# RFID_Brd_02.net
KiCad netlist of a schematic drawn in EAGLE
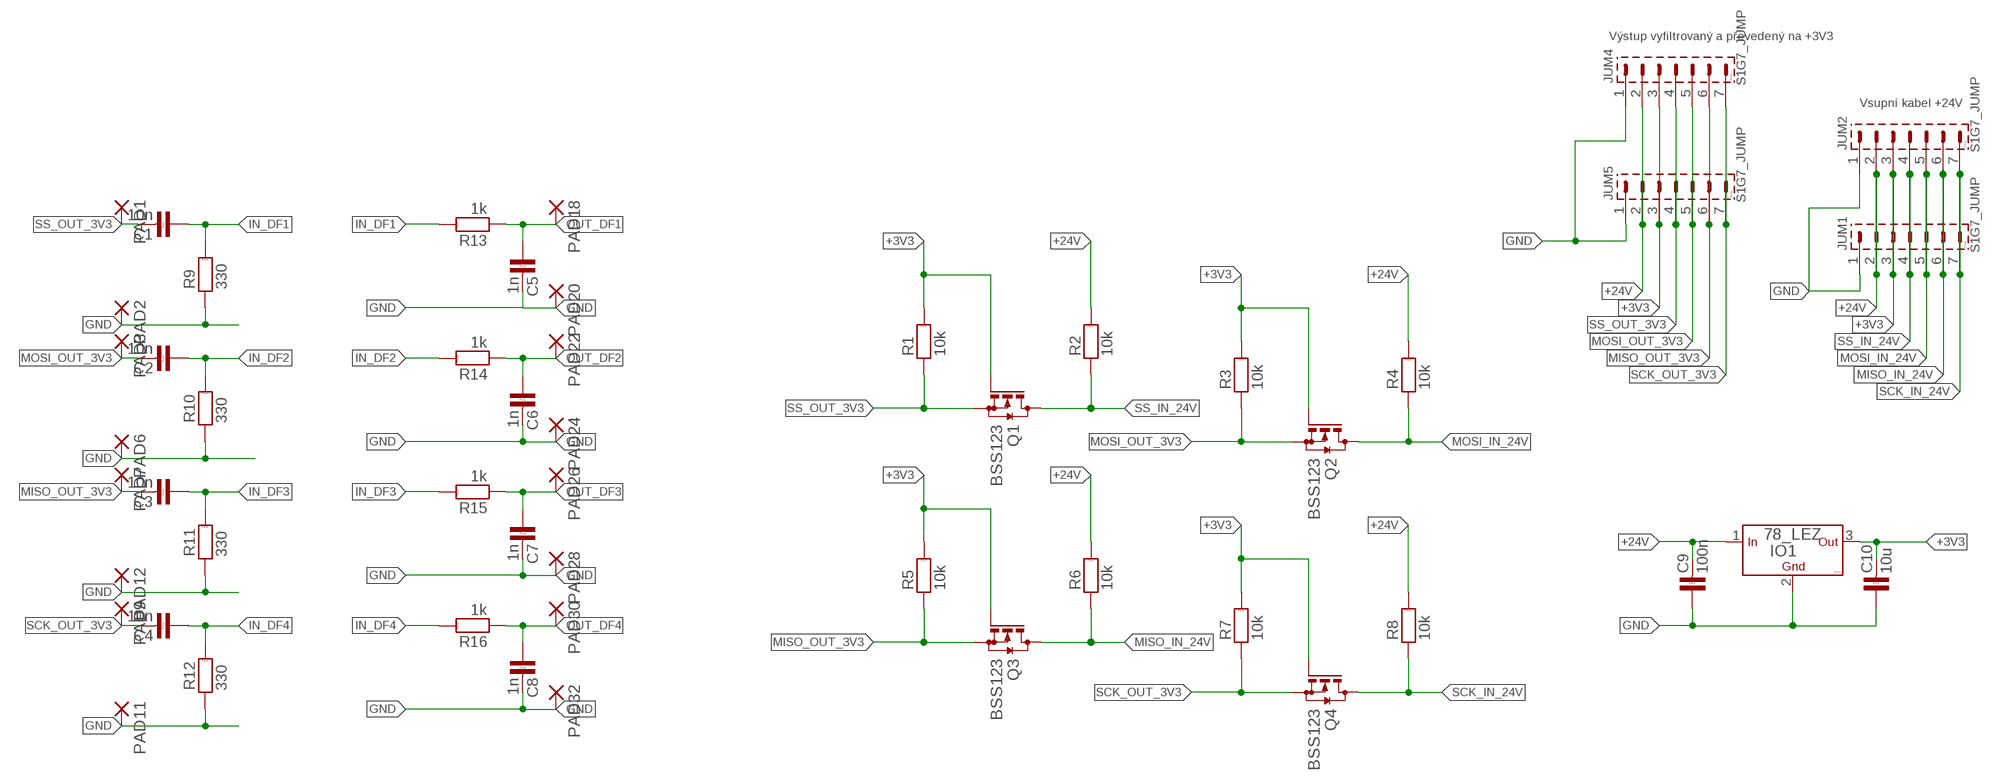
[diagram p0: schematic, sheet 1]

(export (version "E")
  (design (tool "Eeschema 10.0.6"))
  (components
    (comp (ref "C1")
      (value "10n")
      (footprint "eagle-import:1206")
      (libsource (lib "eagle-import") (part "C-KER_1206"))
    )
    (comp (ref "C2")
      (value "10n")
      (footprint "eagle-import:1206")
      (libsource (lib "eagle-import") (part "C-KER_1206"))
    )
    (comp (ref "C3")
      (value "10n")
      (footprint "eagle-import:1206")
      (libsource (lib "eagle-import") (part "C-KER_1206"))
    )
    (comp (ref "C4")
      (value "10n")
      (footprint "eagle-import:1206")
      (libsource (lib "eagle-import") (part "C-KER_1206"))
    )
    (comp (ref "C5")
      (value "1n")
      (footprint "eagle-import:1206")
      (libsource (lib "eagle-import") (part "C-KER_1206"))
    )
    (comp (ref "C6")
      (value "1n")
      (footprint "eagle-import:1206")
      (libsource (lib "eagle-import") (part "C-KER_1206"))
    )
    (comp (ref "C7")
      (value "1n")
      (footprint "eagle-import:1206")
      (libsource (lib "eagle-import") (part "C-KER_1206"))
    )
    (comp (ref "C8")
      (value "1n")
      (footprint "eagle-import:1206")
      (libsource (lib "eagle-import") (part "C-KER_1206"))
    )
    (comp (ref "C9")
      (value "100n")
      (footprint "eagle-import:1206")
      (libsource (lib "eagle-import") (part "C-KER_1206"))
    )
    (comp (ref "C10")
      (value "10u")
      (footprint "eagle-import:1206")
      (libsource (lib "eagle-import") (part "C-KER_1206"))
    )
    (comp (ref "IO1")
      (value "78_LEZ")
      (footprint "eagle-import:TO-220")
      (libsource (lib "eagle-import") (part "78?_LEZ"))
    )
    (comp (ref "JUM1")
      (value "S1G7_JUMP")
      (footprint "eagle-import:S1G7_JUM")
      (libsource (lib "eagle-import") (part "S1G7_JUMP"))
    )
    (comp (ref "JUM2")
      (value "S1G7_JUMP")
      (footprint "eagle-import:S1G7_JUM")
      (libsource (lib "eagle-import") (part "S1G7_JUMP"))
    )
    (comp (ref "JUM4")
      (value "S1G7_JUMP")
      (footprint "eagle-import:S1G7_JUM")
      (libsource (lib "eagle-import") (part "S1G7_JUMP"))
    )
    (comp (ref "JUM5")
      (value "S1G7_JUMP")
      (footprint "eagle-import:S1G7_JUM")
      (libsource (lib "eagle-import") (part "S1G7_JUMP"))
    )
    (comp (ref "PAD1")
      (value "SMD2")
      (footprint "eagle-import:SMD1,27-2,54")
      (libsource (lib "eagle-import") (part "SMD2"))
    )
    (comp (ref "PAD2")
      (value "SMD2")
      (footprint "eagle-import:SMD1,27-2,54")
      (libsource (lib "eagle-import") (part "SMD2"))
    )
    (comp (ref "PAD3")
      (value "SMD2")
      (footprint "eagle-import:SMD1,27-2,54")
      (libsource (lib "eagle-import") (part "SMD2"))
    )
    (comp (ref "PAD6")
      (value "SMD2")
      (footprint "eagle-import:SMD1,27-2,54")
      (libsource (lib "eagle-import") (part "SMD2"))
    )
    (comp (ref "PAD7")
      (value "SMD2")
      (footprint "eagle-import:SMD1,27-2,54")
      (libsource (lib "eagle-import") (part "SMD2"))
    )
    (comp (ref "PAD9")
      (value "SMD2")
      (footprint "eagle-import:SMD1,27-2,54")
      (libsource (lib "eagle-import") (part "SMD2"))
    )
    (comp (ref "PAD11")
      (value "SMD2")
      (footprint "eagle-import:SMD1,27-2,54")
      (libsource (lib "eagle-import") (part "SMD2"))
    )
    (comp (ref "PAD12")
      (value "SMD2")
      (footprint "eagle-import:SMD1,27-2,54")
      (libsource (lib "eagle-import") (part "SMD2"))
    )
    (comp (ref "PAD18")
      (value "SMD2")
      (footprint "eagle-import:SMD1,27-2,54")
      (libsource (lib "eagle-import") (part "SMD2"))
    )
    (comp (ref "PAD20")
      (value "SMD2")
      (footprint "eagle-import:SMD1,27-2,54")
      (libsource (lib "eagle-import") (part "SMD2"))
    )
    (comp (ref "PAD22")
      (value "SMD2")
      (footprint "eagle-import:SMD1,27-2,54")
      (libsource (lib "eagle-import") (part "SMD2"))
    )
    (comp (ref "PAD24")
      (value "SMD2")
      (footprint "eagle-import:SMD1,27-2,54")
      (libsource (lib "eagle-import") (part "SMD2"))
    )
    (comp (ref "PAD26")
      (value "SMD2")
      (footprint "eagle-import:SMD1,27-2,54")
      (libsource (lib "eagle-import") (part "SMD2"))
    )
    (comp (ref "PAD28")
      (value "SMD2")
      (footprint "eagle-import:SMD1,27-2,54")
      (libsource (lib "eagle-import") (part "SMD2"))
    )
    (comp (ref "PAD30")
      (value "SMD2")
      (footprint "eagle-import:SMD1,27-2,54")
      (libsource (lib "eagle-import") (part "SMD2"))
    )
    (comp (ref "PAD32")
      (value "SMD2")
      (footprint "eagle-import:SMD1,27-2,54")
      (libsource (lib "eagle-import") (part "SMD2"))
    )
    (comp (ref "Q1")
      (value "BSS123")
      (footprint "eagle-import:SOT23")
      (libsource (lib "eagle-import") (part "BSS123"))
    )
    (comp (ref "Q2")
      (value "BSS123")
      (footprint "eagle-import:SOT23")
      (libsource (lib "eagle-import") (part "BSS123"))
    )
    (comp (ref "Q3")
      (value "BSS123")
      (footprint "eagle-import:SOT23")
      (libsource (lib "eagle-import") (part "BSS123"))
    )
    (comp (ref "Q4")
      (value "BSS123")
      (footprint "eagle-import:SOT23")
      (libsource (lib "eagle-import") (part "BSS123"))
    )
    (comp (ref "R1")
      (value "10k")
      (footprint "eagle-import:1206")
      (libsource (lib "eagle-import") (part "R_1206"))
    )
    (comp (ref "R2")
      (value "10k")
      (footprint "eagle-import:1206")
      (libsource (lib "eagle-import") (part "R_1206"))
    )
    (comp (ref "R3")
      (value "10k")
      (footprint "eagle-import:1206")
      (libsource (lib "eagle-import") (part "R_1206"))
    )
    (comp (ref "R4")
      (value "10k")
      (footprint "eagle-import:1206")
      (libsource (lib "eagle-import") (part "R_1206"))
    )
    (comp (ref "R5")
      (value "10k")
      (footprint "eagle-import:1206")
      (libsource (lib "eagle-import") (part "R_1206"))
    )
    (comp (ref "R6")
      (value "10k")
      (footprint "eagle-import:1206")
      (libsource (lib "eagle-import") (part "R_1206"))
    )
    (comp (ref "R7")
      (value "10k")
      (footprint "eagle-import:1206")
      (libsource (lib "eagle-import") (part "R_1206"))
    )
    (comp (ref "R8")
      (value "10k")
      (footprint "eagle-import:1206")
      (libsource (lib "eagle-import") (part "R_1206"))
    )
    (comp (ref "R9")
      (value "330")
      (footprint "eagle-import:1206")
      (libsource (lib "eagle-import") (part "R_1206"))
    )
    (comp (ref "R10")
      (value "330")
      (footprint "eagle-import:1206")
      (libsource (lib "eagle-import") (part "R_1206"))
    )
    (comp (ref "R11")
      (value "330")
      (footprint "eagle-import:1206")
      (libsource (lib "eagle-import") (part "R_1206"))
    )
    (comp (ref "R12")
      (value "330")
      (footprint "eagle-import:1206")
      (libsource (lib "eagle-import") (part "R_1206"))
    )
    (comp (ref "R13")
      (value "1k")
      (footprint "eagle-import:1206")
      (libsource (lib "eagle-import") (part "R_1206"))
    )
    (comp (ref "R14")
      (value "1k")
      (footprint "eagle-import:1206")
      (libsource (lib "eagle-import") (part "R_1206"))
    )
    (comp (ref "R15")
      (value "1k")
      (footprint "eagle-import:1206")
      (libsource (lib "eagle-import") (part "R_1206"))
    )
    (comp (ref "R16")
      (value "1k")
      (footprint "eagle-import:1206")
      (libsource (lib "eagle-import") (part "R_1206"))
    )
  )
  (nets
    (net (code "1") (name "+3V3") (class "Default")
      (node (ref "C10") (pin "2") (pinfunction "2_2") (pintype "passive"))
      (node (ref "IO1") (pin "3") (pinfunction "OUT_3") (pintype "passive"))
      (node (ref "JUM1") (pin "3") (pinfunction "3_3") (pintype "passive"))
      (node (ref "JUM2") (pin "3") (pinfunction "3_3") (pintype "passive"))
      (node (ref "JUM4") (pin "3") (pinfunction "3_3") (pintype "passive"))
      (node (ref "JUM5") (pin "3") (pinfunction "3_3") (pintype "passive"))
      (node (ref "Q1") (pin "1") (pinfunction "G_1") (pintype "passive"))
      (node (ref "Q2") (pin "1") (pinfunction "G_1") (pintype "passive"))
      (node (ref "Q3") (pin "1") (pinfunction "G_1") (pintype "passive"))
      (node (ref "Q4") (pin "1") (pinfunction "G_1") (pintype "passive"))
      (node (ref "R1") (pin "2") (pinfunction "2_2") (pintype "passive"))
      (node (ref "R3") (pin "2") (pinfunction "2_2") (pintype "passive"))
      (node (ref "R5") (pin "2") (pinfunction "2_2") (pintype "passive"))
      (node (ref "R7") (pin "2") (pinfunction "2_2") (pintype "passive"))
    )
    (net (code "2") (name "+24V") (class "Default")
      (node (ref "C9") (pin "2") (pinfunction "2_2") (pintype "passive"))
      (node (ref "IO1") (pin "1") (pinfunction "IN_1") (pintype "passive"))
      (node (ref "JUM1") (pin "2") (pinfunction "2_2") (pintype "passive"))
      (node (ref "JUM2") (pin "2") (pinfunction "2_2") (pintype "passive"))
      (node (ref "JUM4") (pin "2") (pinfunction "2_2") (pintype "passive"))
      (node (ref "JUM5") (pin "2") (pinfunction "2_2") (pintype "passive"))
      (node (ref "R2") (pin "2") (pinfunction "2_2") (pintype "passive"))
      (node (ref "R4") (pin "2") (pinfunction "2_2") (pintype "passive"))
      (node (ref "R6") (pin "2") (pinfunction "2_2") (pintype "passive"))
      (node (ref "R8") (pin "2") (pinfunction "2_2") (pintype "passive"))
    )
    (net (code "3") (name "GND") (class "Default")
      (node (ref "C10") (pin "1") (pinfunction "1_1") (pintype "passive"))
      (node (ref "C5") (pin "2") (pinfunction "2_2") (pintype "passive"))
      (node (ref "C6") (pin "2") (pinfunction "2_2") (pintype "passive"))
      (node (ref "C7") (pin "2") (pinfunction "2_2") (pintype "passive"))
      (node (ref "C8") (pin "2") (pinfunction "2_2") (pintype "passive"))
      (node (ref "C9") (pin "1") (pinfunction "1_1") (pintype "passive"))
      (node (ref "IO1") (pin "2") (pinfunction "GND_2") (pintype "passive"))
      (node (ref "JUM1") (pin "1") (pinfunction "1_1") (pintype "passive"))
      (node (ref "JUM2") (pin "1") (pinfunction "1_1") (pintype "passive"))
      (node (ref "JUM4") (pin "1") (pinfunction "1_1") (pintype "passive"))
      (node (ref "JUM5") (pin "1") (pinfunction "1_1") (pintype "passive"))
      (node (ref "PAD11") (pin "1") (pinfunction "P_1") (pintype "passive"))
      (node (ref "PAD12") (pin "1") (pinfunction "P_1") (pintype "passive"))
      (node (ref "PAD2") (pin "1") (pinfunction "P_1") (pintype "passive"))
      (node (ref "PAD20") (pin "1") (pinfunction "P_1") (pintype "passive"))
      (node (ref "PAD24") (pin "1") (pinfunction "P_1") (pintype "passive"))
      (node (ref "PAD28") (pin "1") (pinfunction "P_1") (pintype "passive"))
      (node (ref "PAD32") (pin "1") (pinfunction "P_1") (pintype "passive"))
      (node (ref "PAD6") (pin "1") (pinfunction "P_1") (pintype "passive"))
      (node (ref "R10") (pin "1") (pinfunction "1_1") (pintype "passive"))
      (node (ref "R11") (pin "1") (pinfunction "1_1") (pintype "passive"))
      (node (ref "R12") (pin "1") (pinfunction "1_1") (pintype "passive"))
      (node (ref "R9") (pin "1") (pinfunction "1_1") (pintype "passive"))
    )
    (net (code "4") (name "IN_DF1") (class "Default")
      (node (ref "C1") (pin "1") (pinfunction "1_1") (pintype "passive"))
      (node (ref "R13") (pin "2") (pinfunction "2_2") (pintype "passive"))
      (node (ref "R9") (pin "2") (pinfunction "2_2") (pintype "passive"))
    )
    (net (code "5") (name "IN_DF2") (class "Default")
      (node (ref "C2") (pin "1") (pinfunction "1_1") (pintype "passive"))
      (node (ref "R10") (pin "2") (pinfunction "2_2") (pintype "passive"))
      (node (ref "R14") (pin "2") (pinfunction "2_2") (pintype "passive"))
    )
    (net (code "6") (name "IN_DF3") (class "Default")
      (node (ref "C3") (pin "1") (pinfunction "1_1") (pintype "passive"))
      (node (ref "R11") (pin "2") (pinfunction "2_2") (pintype "passive"))
      (node (ref "R15") (pin "2") (pinfunction "2_2") (pintype "passive"))
    )
    (net (code "7") (name "IN_DF4") (class "Default")
      (node (ref "C4") (pin "1") (pinfunction "1_1") (pintype "passive"))
      (node (ref "R12") (pin "2") (pinfunction "2_2") (pintype "passive"))
      (node (ref "R16") (pin "2") (pinfunction "2_2") (pintype "passive"))
    )
    (net (code "8") (name "MISO_IN_24V") (class "Default")
      (node (ref "JUM1") (pin "6") (pinfunction "6_6") (pintype "passive"))
      (node (ref "JUM2") (pin "6") (pinfunction "6_6") (pintype "passive"))
      (node (ref "Q3") (pin "3") (pinfunction "D_3") (pintype "passive"))
      (node (ref "R6") (pin "1") (pinfunction "1_1") (pintype "passive"))
    )
    (net (code "9") (name "MISO_OUT_3V3") (class "Default")
      (node (ref "C3") (pin "2") (pinfunction "2_2") (pintype "passive"))
      (node (ref "JUM4") (pin "6") (pinfunction "6_6") (pintype "passive"))
      (node (ref "JUM5") (pin "6") (pinfunction "6_6") (pintype "passive"))
      (node (ref "PAD7") (pin "1") (pinfunction "P_1") (pintype "passive"))
      (node (ref "Q3") (pin "2") (pinfunction "S_2") (pintype "passive"))
      (node (ref "R5") (pin "1") (pinfunction "1_1") (pintype "passive"))
    )
    (net (code "10") (name "MOSI_IN_24V") (class "Default")
      (node (ref "JUM1") (pin "5") (pinfunction "5_5") (pintype "passive"))
      (node (ref "JUM2") (pin "5") (pinfunction "5_5") (pintype "passive"))
      (node (ref "Q2") (pin "3") (pinfunction "D_3") (pintype "passive"))
      (node (ref "R4") (pin "1") (pinfunction "1_1") (pintype "passive"))
    )
    (net (code "11") (name "MOSI_OUT_3V3") (class "Default")
      (node (ref "C2") (pin "2") (pinfunction "2_2") (pintype "passive"))
      (node (ref "JUM4") (pin "5") (pinfunction "5_5") (pintype "passive"))
      (node (ref "JUM5") (pin "5") (pinfunction "5_5") (pintype "passive"))
      (node (ref "PAD3") (pin "1") (pinfunction "P_1") (pintype "passive"))
      (node (ref "Q2") (pin "2") (pinfunction "S_2") (pintype "passive"))
      (node (ref "R3") (pin "1") (pinfunction "1_1") (pintype "passive"))
    )
    (net (code "12") (name "OUT_DF1") (class "Default")
      (node (ref "C5") (pin "1") (pinfunction "1_1") (pintype "passive"))
      (node (ref "PAD18") (pin "1") (pinfunction "P_1") (pintype "passive"))
      (node (ref "R13") (pin "1") (pinfunction "1_1") (pintype "passive"))
    )
    (net (code "13") (name "OUT_DF2") (class "Default")
      (node (ref "C6") (pin "1") (pinfunction "1_1") (pintype "passive"))
      (node (ref "PAD22") (pin "1") (pinfunction "P_1") (pintype "passive"))
      (node (ref "R14") (pin "1") (pinfunction "1_1") (pintype "passive"))
    )
    (net (code "14") (name "OUT_DF3") (class "Default")
      (node (ref "C7") (pin "1") (pinfunction "1_1") (pintype "passive"))
      (node (ref "PAD26") (pin "1") (pinfunction "P_1") (pintype "passive"))
      (node (ref "R15") (pin "1") (pinfunction "1_1") (pintype "passive"))
    )
    (net (code "15") (name "OUT_DF4") (class "Default")
      (node (ref "C8") (pin "1") (pinfunction "1_1") (pintype "passive"))
      (node (ref "PAD30") (pin "1") (pinfunction "P_1") (pintype "passive"))
      (node (ref "R16") (pin "1") (pinfunction "1_1") (pintype "passive"))
    )
    (net (code "16") (name "SCK_IN_24V") (class "Default")
      (node (ref "JUM1") (pin "7") (pinfunction "7_7") (pintype "passive"))
      (node (ref "JUM2") (pin "7") (pinfunction "7_7") (pintype "passive"))
      (node (ref "Q4") (pin "3") (pinfunction "D_3") (pintype "passive"))
      (node (ref "R8") (pin "1") (pinfunction "1_1") (pintype "passive"))
    )
    (net (code "17") (name "SCK_OUT_3V3") (class "Default")
      (node (ref "C4") (pin "2") (pinfunction "2_2") (pintype "passive"))
      (node (ref "JUM4") (pin "7") (pinfunction "7_7") (pintype "passive"))
      (node (ref "JUM5") (pin "7") (pinfunction "7_7") (pintype "passive"))
      (node (ref "PAD9") (pin "1") (pinfunction "P_1") (pintype "passive"))
      (node (ref "Q4") (pin "2") (pinfunction "S_2") (pintype "passive"))
      (node (ref "R7") (pin "1") (pinfunction "1_1") (pintype "passive"))
    )
    (net (code "18") (name "SS_IN_24V") (class "Default")
      (node (ref "JUM1") (pin "4") (pinfunction "4_4") (pintype "passive"))
      (node (ref "JUM2") (pin "4") (pinfunction "4_4") (pintype "passive"))
      (node (ref "Q1") (pin "3") (pinfunction "D_3") (pintype "passive"))
      (node (ref "R2") (pin "1") (pinfunction "1_1") (pintype "passive"))
    )
    (net (code "19") (name "SS_OUT_3V3") (class "Default")
      (node (ref "C1") (pin "2") (pinfunction "2_2") (pintype "passive"))
      (node (ref "JUM4") (pin "4") (pinfunction "4_4") (pintype "passive"))
      (node (ref "JUM5") (pin "4") (pinfunction "4_4") (pintype "passive"))
      (node (ref "PAD1") (pin "1") (pinfunction "P_1") (pintype "passive"))
      (node (ref "Q1") (pin "2") (pinfunction "S_2") (pintype "passive"))
      (node (ref "R1") (pin "1") (pinfunction "1_1") (pintype "passive"))
    )
  )
)
